# Control.net
KiCad netlist of a schematic drawn in Altium Designer
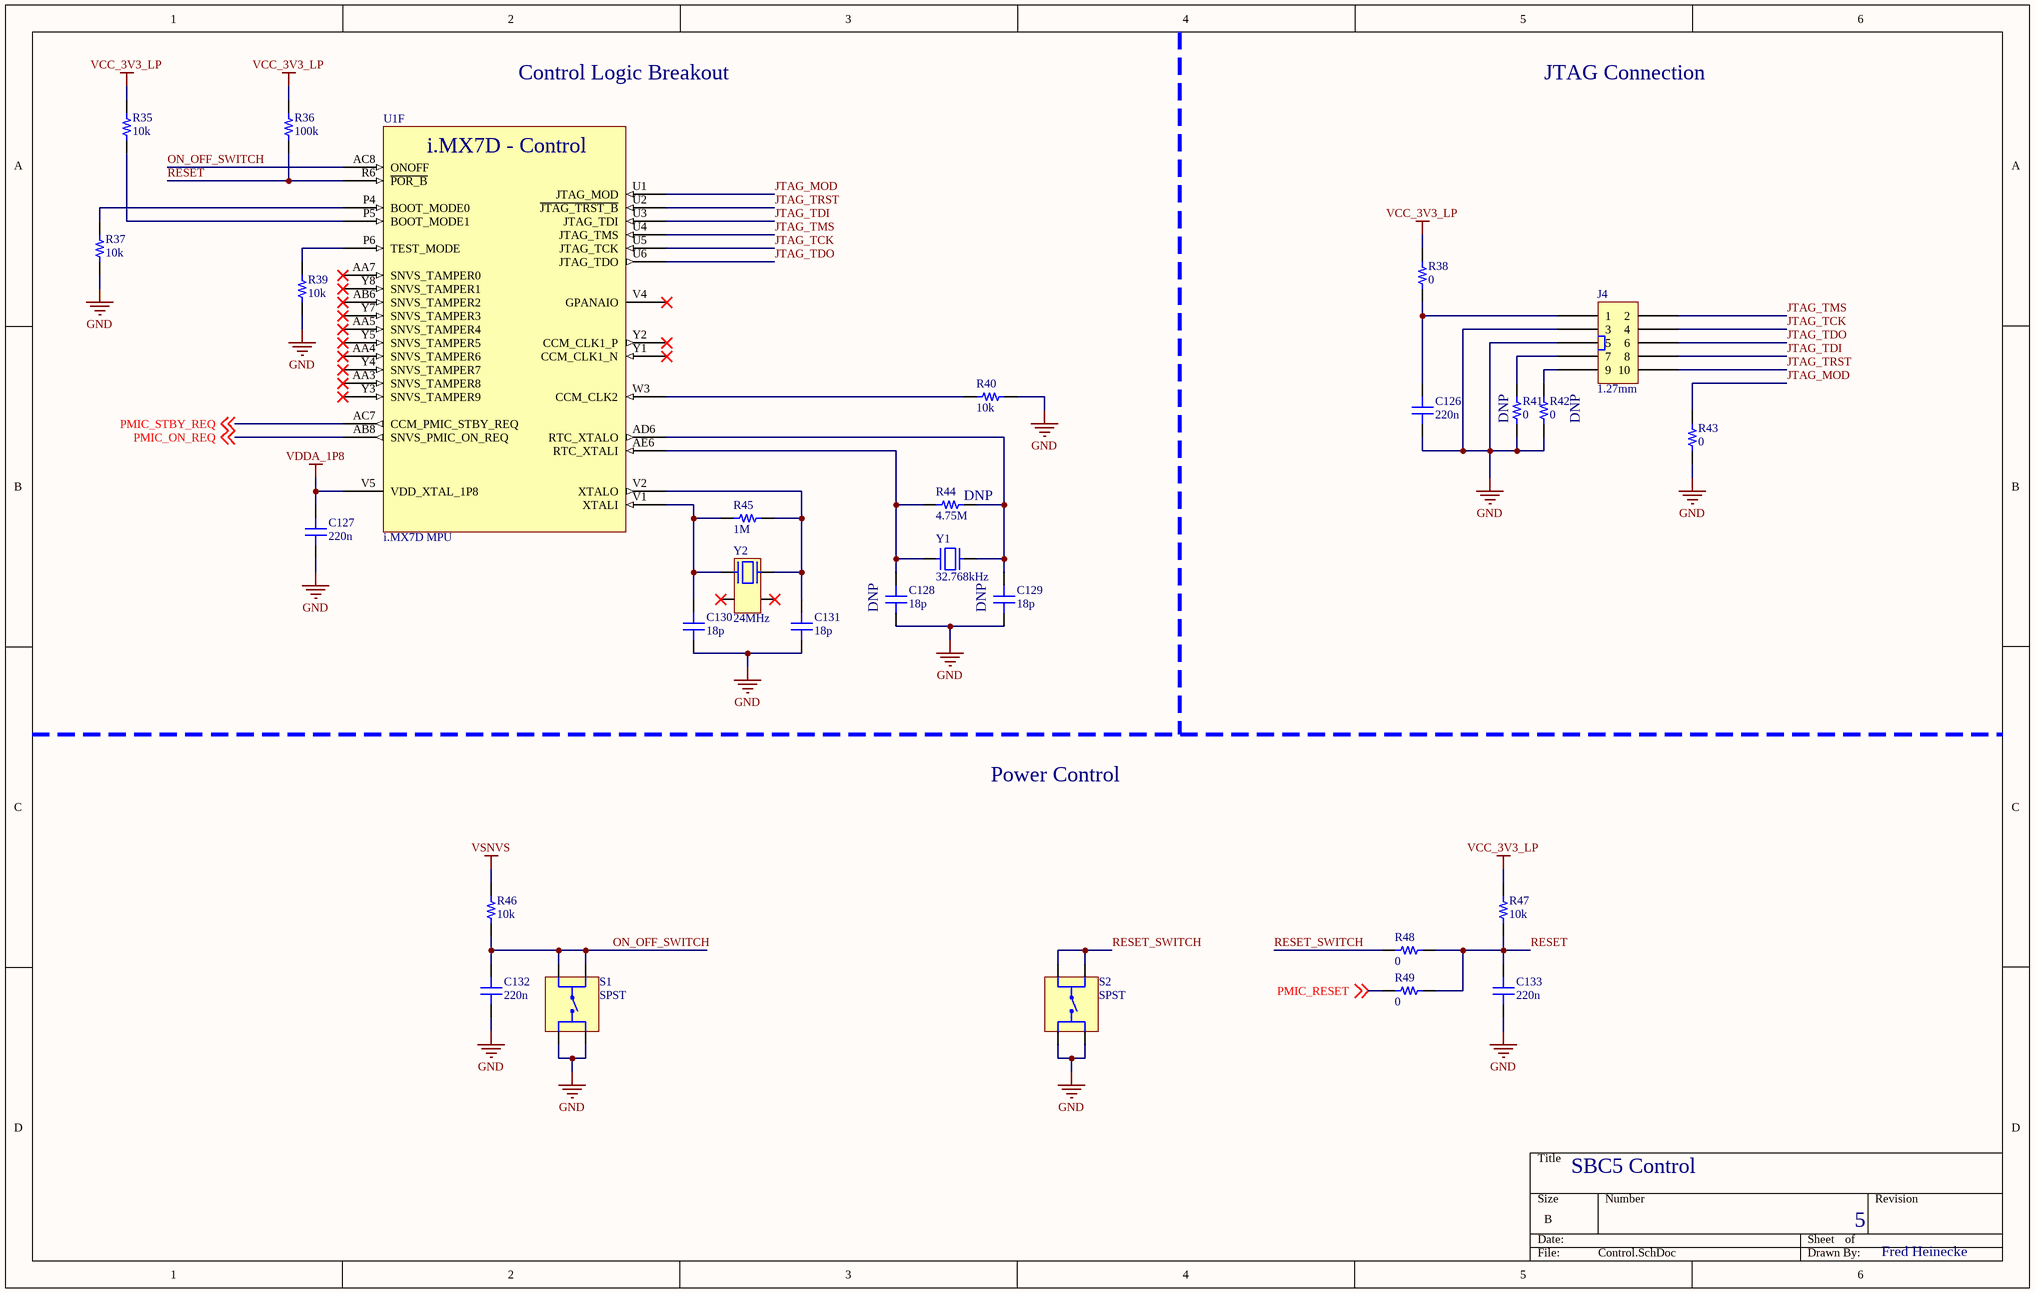
[diagram p0: Control.SchDoc]

(export (version "E")
  (design (tool "Eeschema 10.0.6"))
  (components
    (comp (ref "C126")
      (value "220n")
      (footprint "C0201")
      (description "Cap Ceramic Monolithic 0.22uF 16VDC 10% SMD Paper T/R")
      (fields
        (field (name "MANUFACTURER") "Murata")
        (field (name "MANUFACTURER PART NUMBER") "GRM033R61C224KE14D")
      )
      (libsource (lib "SBC5") (part "GRM033R61C224KE14D"))
    )
    (comp (ref "C127")
      (value "220n")
      (footprint "C0201")
      (description "Cap Ceramic Monolithic 0.22uF 16VDC 10% SMD Paper T/R")
      (fields
        (field (name "MANUFACTURER") "Murata")
        (field (name "MANUFACTURER PART NUMBER") "GRM033R61C224KE14D")
      )
      (libsource (lib "SBC5") (part "GRM033R61C224KE14D"))
    )
    (comp (ref "C128")
      (value "18p")
      (footprint "C0402")
      (description "CAP CER 18PF 50V C0G/NP0 0402")
      (fields
        (field (name "MANUFACTURER") "Samsung")
        (field (name "MANUFACTURER PART NUMBER") "CL05C180JB5NNNC")
      )
      (libsource (lib "SBC5") (part "CL05C180JB5NNNC"))
    )
    (comp (ref "C129")
      (value "18p")
      (footprint "C0402")
      (description "CAP CER 18PF 50V C0G/NP0 0402")
      (fields
        (field (name "MANUFACTURER") "Samsung")
        (field (name "MANUFACTURER PART NUMBER") "CL05C180JB5NNNC")
      )
      (libsource (lib "SBC5") (part "CL05C180JB5NNNC"))
    )
    (comp (ref "C130")
      (value "18p")
      (footprint "C0402")
      (description "CAP CER 18PF 50V C0G/NP0 0402")
      (fields
        (field (name "MANUFACTURER") "Samsung")
        (field (name "MANUFACTURER PART NUMBER") "CL05C180JB5NNNC")
      )
      (libsource (lib "SBC5") (part "CL05C180JB5NNNC"))
    )
    (comp (ref "C131")
      (value "18p")
      (footprint "C0402")
      (description "CAP CER 18PF 50V C0G/NP0 0402")
      (fields
        (field (name "MANUFACTURER") "Samsung")
        (field (name "MANUFACTURER PART NUMBER") "CL05C180JB5NNNC")
      )
      (libsource (lib "SBC5") (part "CL05C180JB5NNNC"))
    )
    (comp (ref "C132")
      (value "220n")
      (footprint "C0201")
      (description "Cap Ceramic Monolithic 0.22uF 16VDC 10% SMD Paper T/R")
      (fields
        (field (name "MANUFACTURER") "Murata")
        (field (name "MANUFACTURER PART NUMBER") "GRM033R61C224KE14D")
      )
      (libsource (lib "SBC5") (part "GRM033R61C224KE14D"))
    )
    (comp (ref "C133")
      (value "220n")
      (footprint "C0201")
      (description "Cap Ceramic Monolithic 0.22uF 16VDC 10% SMD Paper T/R")
      (fields
        (field (name "MANUFACTURER") "Murata")
        (field (name "MANUFACTURER PART NUMBER") "GRM033R61C224KE14D")
      )
      (libsource (lib "SBC5") (part "GRM033R61C224KE14D"))
    )
    (comp (ref "J4")
      (value "1.27mm")
      (footprint "20021521-00010T1LF")
      (description "CONN HEADER SMD 10POS 1.27MM")
      (fields
        (field (name "MANUFACTURER") "Amphenol FCI")
        (field (name "MANUFACTURER PART NUMBER") "20021521-00010T1LF")
      )
      (libsource (lib "SBC5") (part "20021521-00010T1LF"))
    )
    (comp (ref "R35")
      (value "10k")
      (footprint "R0201")
      (description "RES 10K OHM 1% 1/20W 0201")
      (fields
        (field (name "MANUFACTURER") "Stackpole Electronics")
        (field (name "MANUFACTURER PART NUMBER") "RMCF0201FT10K0")
      )
      (libsource (lib "SBC5") (part "RMCF0201FT10K0"))
    )
    (comp (ref "R36")
      (value "100k")
      (footprint "R0201")
      (description "PANASONIC - ERJ1GNF1003C - RES, 100K, 1%, 0.05W, 0201, THICK FILM")
      (fields
        (field (name "MANUFACTURER") "Panasonic")
        (field (name "MANUFACTURER PART NUMBER") "ERJ-1GNF1003C")
      )
      (libsource (lib "SBC5") (part "ERJ-1GNF1003C"))
    )
    (comp (ref "R37")
      (value "10k")
      (footprint "R0201")
      (description "RES 10K OHM 1% 1/20W 0201")
      (fields
        (field (name "MANUFACTURER") "Stackpole Electronics")
        (field (name "MANUFACTURER PART NUMBER") "RMCF0201FT10K0")
      )
      (libsource (lib "SBC5") (part "RMCF0201FT10K0"))
    )
    (comp (ref "R38")
      (value "0")
      (footprint "R1210")
      (description "RES 0.0 OHM 1/2W 1210 SMD")
      (fields
        (field (name "MANUFACTURER") "Stackpole Electronics")
        (field (name "MANUFACTURER PART NUMBER") "RMCF1210ZT0R00")
      )
      (libsource (lib "SBC5") (part "RMCF1210ZT0R00"))
    )
    (comp (ref "R39")
      (value "10k")
      (footprint "R0201")
      (description "RES 10K OHM 1% 1/20W 0201")
      (fields
        (field (name "MANUFACTURER") "Stackpole Electronics")
        (field (name "MANUFACTURER PART NUMBER") "RMCF0201FT10K0")
      )
      (libsource (lib "SBC5") (part "RMCF0201FT10K0"))
    )
    (comp (ref "R40")
      (value "10k")
      (footprint "R0201")
      (description "RES 10K OHM 1% 1/20W 0201")
      (fields
        (field (name "MANUFACTURER") "Stackpole Electronics")
        (field (name "MANUFACTURER PART NUMBER") "RMCF0201FT10K0")
      )
      (libsource (lib "SBC5") (part "RMCF0201FT10K0"))
    )
    (comp (ref "R41")
      (value "0")
      (footprint "R0402")
      (description "RES 0 OHM JUMPER 1/16W 0402")
      (fields
        (field (name "MANUFACTURER") "Stackpole Electronics")
        (field (name "MANUFACTURER PART NUMBER") "RMCF0402ZT0R00")
      )
      (libsource (lib "SBC5") (part "RMCF0402ZT0R00"))
    )
    (comp (ref "R42")
      (value "0")
      (footprint "R0402")
      (description "RES 0 OHM JUMPER 1/16W 0402")
      (fields
        (field (name "MANUFACTURER") "Stackpole Electronics")
        (field (name "MANUFACTURER PART NUMBER") "RMCF0402ZT0R00")
      )
      (libsource (lib "SBC5") (part "RMCF0402ZT0R00"))
    )
    (comp (ref "R43")
      (value "0")
      (footprint "R0402")
      (description "RES 0 OHM JUMPER 1/16W 0402")
      (fields
        (field (name "MANUFACTURER") "Stackpole Electronics")
        (field (name "MANUFACTURER PART NUMBER") "RMCF0402ZT0R00")
      )
      (libsource (lib "SBC5") (part "RMCF0402ZT0R00"))
    )
    (comp (ref "R44")
      (value "4.75M")
      (footprint "R0402")
      (description "Thick Film Resistors - SMD 4.75M OHM 1%")
      (fields
        (field (name "MANUFACTURER") "Yageo")
        (field (name "MANUFACTURER PART NUMBER") "RC0402FR-074M75L")
      )
      (libsource (lib "SBC5") (part "RC0402FR-074M75L"))
    )
    (comp (ref "R45")
      (value "1M")
      (footprint "R0402")
      (description "RES SMD 1M OHM 1% 1/16W 0402")
      (fields
        (field (name "MANUFACTURER") "Yageo")
        (field (name "MANUFACTURER PART NUMBER") "RC0402FR-071ML")
      )
      (libsource (lib "SBC5") (part "RC0402FR-071ML"))
    )
    (comp (ref "R46")
      (value "10k")
      (footprint "R0201")
      (description "RES 10K OHM 1% 1/20W 0201")
      (fields
        (field (name "MANUFACTURER") "Stackpole Electronics")
        (field (name "MANUFACTURER PART NUMBER") "RMCF0201FT10K0")
      )
      (libsource (lib "SBC5") (part "RMCF0201FT10K0"))
    )
    (comp (ref "R47")
      (value "10k")
      (footprint "R0201")
      (description "RES 10K OHM 1% 1/20W 0201")
      (fields
        (field (name "MANUFACTURER") "Stackpole Electronics")
        (field (name "MANUFACTURER PART NUMBER") "RMCF0201FT10K0")
      )
      (libsource (lib "SBC5") (part "RMCF0201FT10K0"))
    )
    (comp (ref "R48")
      (value "0")
      (footprint "R0402")
      (description "RES 0 OHM JUMPER 1/16W 0402")
      (fields
        (field (name "MANUFACTURER") "Stackpole Electronics")
        (field (name "MANUFACTURER PART NUMBER") "RMCF0402ZT0R00")
      )
      (libsource (lib "SBC5") (part "RMCF0402ZT0R00"))
    )
    (comp (ref "R49")
      (value "0")
      (footprint "R0402")
      (description "RES 0 OHM JUMPER 1/16W 0402")
      (fields
        (field (name "MANUFACTURER") "Stackpole Electronics")
        (field (name "MANUFACTURER PART NUMBER") "RMCF0402ZT0R00")
      )
      (libsource (lib "SBC5") (part "RMCF0402ZT0R00"))
    )
    (comp (ref "S1")
      (value "SPST")
      (footprint "1825910-7")
      (fields
        (field (name "MANUFACTURER") "TE Connectivity")
        (field (name "MANUFACTURER PART NUMBER") "1825910-7")
      )
      (libsource (lib "SBC5") (part "1825910-7"))
    )
    (comp (ref "S2")
      (value "SPST")
      (footprint "1825910-7")
      (fields
        (field (name "MANUFACTURER") "TE Connectivity")
        (field (name "MANUFACTURER PART NUMBER") "1825910-7")
      )
      (libsource (lib "SBC5") (part "1825910-7"))
    )
    (comp (ref "U1")
      (value "i.MX7D MPU")
      (footprint "BGA541C75P25X25_1900X1900X140")
      (description "Heterogeneous Multicore Processing Architecture")
      (fields
        (field (name "MANUFACTURER") "NXP Freescale")
        (field (name "MANUFACTURER PART NUMBER") "MCIMX7D2DVM12SD")
      )
      (libsource (lib "SBC5") (part "MCIMX7D2DVM12SD"))
    )
    (comp (ref "Y1")
      (value "32.768kHz")
      (footprint "CM7V-T1A")
      (description "32.768 kHz crystal oscillator, 12.5 pF 50k ESR")
      (fields
        (field (name "MANUFACTURER") "Micro Crystal")
        (field (name "MANUFACTURER PART NUMBER") "CM7VT1A-LOWESR-32.768KHZ-12.5PF-20-TA-QC")
      )
      (libsource (lib "SBC5") (part "CM7VT1A-LOWESR-32.768KHZ-12.5PF-20-TA-QC"))
    )
    (comp (ref "Y2")
      (value "24MHz")
      (footprint "FQ5032B")
      (description "Crystal 24MHz ±30ppm (Tol) ±30ppm (Stability) 20pF FUND 50Ohm 4-Pin SMD T/R")
      (fields
        (field (name "MANUFACTURER") "Fox Electronics")
        (field (name "MANUFACTURER PART NUMBER") "FC5BQCCMC24.0-T1")
      )
      (libsource (lib "SBC5") (part "FC5BQCCMC24.0-T1"))
    )
  )
  (nets
    (net (code "1") (name "/JTAG_MOD") (class "Default")
      (node (ref "R43") (pin "2") (pinfunction "2_2") (pintype "passive"))
      (node (ref "U1") (pin "U1") (pinfunction "JTAG_MOD_U1") (pintype "input"))
    )
    (net (code "2") (name "/JTAG_TCK") (class "Default")
      (node (ref "J4") (pin "4") (pinfunction "4_4") (pintype "passive"))
      (node (ref "U1") (pin "U5") (pinfunction "JTAG_TCK_U5") (pintype "input"))
    )
    (net (code "3") (name "/JTAG_TDI") (class "Default")
      (node (ref "J4") (pin "8") (pinfunction "8_8") (pintype "passive"))
      (node (ref "U1") (pin "U3") (pinfunction "JTAG_TDI_U3") (pintype "input"))
    )
    (net (code "4") (name "/JTAG_TDO") (class "Default")
      (node (ref "J4") (pin "6") (pinfunction "6_6") (pintype "passive"))
      (node (ref "U1") (pin "U6") (pinfunction "JTAG_TDO_U6") (pintype "output"))
    )
    (net (code "5") (name "/JTAG_TMS") (class "Default")
      (node (ref "J4") (pin "2") (pinfunction "2_2") (pintype "passive"))
      (node (ref "U1") (pin "U4") (pinfunction "JTAG_TMS_U4") (pintype "input"))
    )
    (net (code "6") (name "/JTAG_TRST") (class "Default")
      (node (ref "J4") (pin "10") (pinfunction "10_10") (pintype "passive"))
      (node (ref "U1") (pin "U2") (pinfunction "~{JTAG_TRST_B}_U2") (pintype "input"))
    )
    (net (code "7") (name "/ON_OFF_SWITCH") (class "Default")
      (node (ref "C132") (pin "2") (pinfunction "2_2") (pintype "passive"))
      (node (ref "R46") (pin "1") (pinfunction "1_1") (pintype "passive"))
      (node (ref "S1") (pin "1") (pintype "passive"))
      (node (ref "S1") (pin "2") (pintype "passive"))
      (node (ref "U1") (pin "AC8") (pinfunction "ONOFF_AC8") (pintype "input"))
    )
    (net (code "8") (name "/RESET") (class "Default")
      (node (ref "C133") (pin "2") (pinfunction "2_2") (pintype "passive"))
      (node (ref "R36") (pin "1") (pinfunction "1_1") (pintype "passive"))
      (node (ref "R47") (pin "1") (pinfunction "1_1") (pintype "passive"))
      (node (ref "R48") (pin "2") (pinfunction "2_2") (pintype "passive"))
      (node (ref "R49") (pin "2") (pinfunction "2_2") (pintype "passive"))
      (node (ref "U1") (pin "R6") (pinfunction "~{POR_B}_R6") (pintype "input"))
    )
    (net (code "9") (name "/RESET_SWITCH") (class "Default")
      (node (ref "R48") (pin "1") (pinfunction "1_1") (pintype "passive"))
      (node (ref "S2") (pin "1") (pintype "passive"))
      (node (ref "S2") (pin "2") (pintype "passive"))
    )
    (net (code "10") (name "GND") (class "Default")
      (node (ref "C126") (pin "1") (pinfunction "1_1") (pintype "passive"))
      (node (ref "C127") (pin "1") (pinfunction "1_1") (pintype "passive"))
      (node (ref "C128") (pin "1") (pinfunction "1_1") (pintype "passive"))
      (node (ref "C129") (pin "1") (pinfunction "1_1") (pintype "passive"))
      (node (ref "C130") (pin "1") (pinfunction "1_1") (pintype "passive"))
      (node (ref "C131") (pin "1") (pinfunction "1_1") (pintype "passive"))
      (node (ref "C132") (pin "1") (pinfunction "1_1") (pintype "passive"))
      (node (ref "C133") (pin "1") (pinfunction "1_1") (pintype "passive"))
      (node (ref "J4") (pin "3") (pinfunction "3_3") (pintype "passive"))
      (node (ref "J4") (pin "5") (pinfunction "5_5") (pintype "passive"))
      (node (ref "R37") (pin "1") (pinfunction "1_1") (pintype "passive"))
      (node (ref "R39") (pin "1") (pinfunction "1_1") (pintype "passive"))
      (node (ref "R40") (pin "2") (pinfunction "2_2") (pintype "passive"))
      (node (ref "R41") (pin "1") (pinfunction "1_1") (pintype "passive"))
      (node (ref "R42") (pin "1") (pinfunction "1_1") (pintype "passive"))
      (node (ref "R43") (pin "1") (pinfunction "1_1") (pintype "passive"))
      (node (ref "S1") (pin "3") (pintype "passive"))
      (node (ref "S1") (pin "4") (pintype "passive"))
      (node (ref "S2") (pin "3") (pintype "passive"))
      (node (ref "S2") (pin "4") (pintype "passive"))
    )
    (net (code "11") (name "Net-(C126-Pad2)") (class "Default")
      (node (ref "C126") (pin "2") (pinfunction "2_2") (pintype "passive"))
      (node (ref "J4") (pin "1") (pinfunction "1_1") (pintype "passive"))
      (node (ref "R38") (pin "1") (pinfunction "1_1") (pintype "passive"))
    )
    (net (code "12") (name "Net-(J4-Pad7)") (class "Default")
      (node (ref "J4") (pin "7") (pinfunction "7_7") (pintype "passive"))
      (node (ref "R41") (pin "2") (pinfunction "2_2") (pintype "passive"))
    )
    (net (code "13") (name "Net-(J4-Pad9)") (class "Default")
      (node (ref "J4") (pin "9") (pinfunction "9_9") (pintype "passive"))
      (node (ref "R42") (pin "2") (pinfunction "2_2") (pintype "passive"))
    )
    (net (code "14") (name "Net-(U1F-BOOT_MODE0)") (class "Default")
      (node (ref "R37") (pin "2") (pinfunction "2_2") (pintype "passive"))
      (node (ref "U1") (pin "P4") (pinfunction "BOOT_MODE0_P4") (pintype "input"))
    )
    (net (code "15") (name "Net-(U1F-BOOT_MODE1)") (class "Default")
      (node (ref "R35") (pin "1") (pinfunction "1_1") (pintype "passive"))
      (node (ref "U1") (pin "P5") (pinfunction "BOOT_MODE1_P5") (pintype "input"))
    )
    (net (code "16") (name "Net-(U1F-CCM_CLK2)") (class "Default")
      (node (ref "R40") (pin "1") (pinfunction "1_1") (pintype "passive"))
      (node (ref "U1") (pin "W3") (pinfunction "CCM_CLK2_W3") (pintype "input"))
    )
    (net (code "17") (name "Net-(U1F-RTC_XTALI)") (class "Default")
      (node (ref "C128") (pin "2") (pinfunction "2_2") (pintype "passive"))
      (node (ref "R44") (pin "1") (pinfunction "1_1") (pintype "passive"))
      (node (ref "U1") (pin "AE6") (pinfunction "RTC_XTALI_AE6") (pintype "input"))
      (node (ref "Y1") (pin "1") (pinfunction "1_1") (pintype "passive"))
    )
    (net (code "18") (name "Net-(U1F-RTC_XTALO)") (class "Default")
      (node (ref "C129") (pin "2") (pinfunction "2_2") (pintype "passive"))
      (node (ref "R44") (pin "2") (pinfunction "2_2") (pintype "passive"))
      (node (ref "U1") (pin "AD6") (pinfunction "RTC_XTALO_AD6") (pintype "output"))
      (node (ref "Y1") (pin "2") (pinfunction "2_2") (pintype "passive"))
    )
    (net (code "19") (name "Net-(U1F-TEST_MODE)") (class "Default")
      (node (ref "R39") (pin "2") (pinfunction "2_2") (pintype "passive"))
      (node (ref "U1") (pin "P6") (pinfunction "TEST_MODE_P6") (pintype "input"))
    )
    (net (code "20") (name "Net-(U1F-XTALI)") (class "Default")
      (node (ref "C130") (pin "2") (pinfunction "2_2") (pintype "passive"))
      (node (ref "R45") (pin "1") (pinfunction "1_1") (pintype "passive"))
      (node (ref "U1") (pin "V1") (pinfunction "XTALI_V1") (pintype "input"))
      (node (ref "Y2") (pin "1") (pinfunction "1_1") (pintype "passive"))
    )
    (net (code "21") (name "Net-(U1F-XTALO)") (class "Default")
      (node (ref "C131") (pin "2") (pinfunction "2_2") (pintype "passive"))
      (node (ref "R45") (pin "2") (pinfunction "2_2") (pintype "passive"))
      (node (ref "U1") (pin "V2") (pinfunction "XTALO_V2") (pintype "output"))
      (node (ref "Y2") (pin "3") (pinfunction "3_3") (pintype "passive"))
    )
    (net (code "22") (name "PMIC_ON_REQ") (class "Default")
      (node (ref "U1") (pin "AB8") (pinfunction "SNVS_PMIC_ON_REQ_AB8") (pintype "output"))
    )
    (net (code "23") (name "PMIC_RESET") (class "Default")
      (node (ref "R49") (pin "1") (pinfunction "1_1") (pintype "passive"))
    )
    (net (code "24") (name "PMIC_STBY_REQ") (class "Default")
      (node (ref "U1") (pin "AC7") (pinfunction "CCM_PMIC_STBY_REQ_AC7") (pintype "output"))
    )
    (net (code "25") (name "VCC_3V3_LP") (class "Default")
      (node (ref "R35") (pin "2") (pinfunction "2_2") (pintype "passive"))
      (node (ref "R36") (pin "2") (pinfunction "2_2") (pintype "passive"))
      (node (ref "R38") (pin "2") (pinfunction "2_2") (pintype "passive"))
      (node (ref "R47") (pin "2") (pinfunction "2_2") (pintype "passive"))
    )
    (net (code "26") (name "VDDA_1P8") (class "Default")
      (node (ref "C127") (pin "2") (pinfunction "2_2") (pintype "passive"))
      (node (ref "U1") (pin "V5") (pinfunction "VDD_XTAL_1P8_V5") (pintype "passive"))
    )
    (net (code "27") (name "VSNVS") (class "Default")
      (node (ref "R46") (pin "2") (pinfunction "2_2") (pintype "passive"))
    )
    (net (code "28") (name "unconnected-(U1F-CCM_CLK1_N-PadY1)") (class "Default")
      (node (ref "U1") (pin "Y1") (pinfunction "CCM_CLK1_N_Y1") (pintype "input+no_connect"))
    )
    (net (code "29") (name "unconnected-(U1F-CCM_CLK1_P-PadY2)") (class "Default")
      (node (ref "U1") (pin "Y2") (pinfunction "CCM_CLK1_P_Y2") (pintype "output+no_connect"))
    )
    (net (code "30") (name "unconnected-(U1F-GPANAIO-PadV4)") (class "Default")
      (node (ref "U1") (pin "V4") (pinfunction "GPANAIO_V4") (pintype "passive+no_connect"))
    )
    (net (code "31") (name "unconnected-(U1F-SNVS_TAMPER0-PadAA7)") (class "Default")
      (node (ref "U1") (pin "AA7") (pinfunction "SNVS_TAMPER0_AA7") (pintype "input+no_connect"))
    )
    (net (code "32") (name "unconnected-(U1F-SNVS_TAMPER1-PadY8)") (class "Default")
      (node (ref "U1") (pin "Y8") (pinfunction "SNVS_TAMPER1_Y8") (pintype "input+no_connect"))
    )
    (net (code "33") (name "unconnected-(U1F-SNVS_TAMPER2-PadAB6)") (class "Default")
      (node (ref "U1") (pin "AB6") (pinfunction "SNVS_TAMPER2_AB6") (pintype "input+no_connect"))
    )
    (net (code "34") (name "unconnected-(U1F-SNVS_TAMPER3-PadY7)") (class "Default")
      (node (ref "U1") (pin "Y7") (pinfunction "SNVS_TAMPER3_Y7") (pintype "input+no_connect"))
    )
    (net (code "35") (name "unconnected-(U1F-SNVS_TAMPER4-PadAA5)") (class "Default")
      (node (ref "U1") (pin "AA5") (pinfunction "SNVS_TAMPER4_AA5") (pintype "input+no_connect"))
    )
    (net (code "36") (name "unconnected-(U1F-SNVS_TAMPER5-PadY5)") (class "Default")
      (node (ref "U1") (pin "Y5") (pinfunction "SNVS_TAMPER5_Y5") (pintype "input+no_connect"))
    )
    (net (code "37") (name "unconnected-(U1F-SNVS_TAMPER6-PadAA4)") (class "Default")
      (node (ref "U1") (pin "AA4") (pinfunction "SNVS_TAMPER6_AA4") (pintype "input+no_connect"))
    )
    (net (code "38") (name "unconnected-(U1F-SNVS_TAMPER7-PadY4)") (class "Default")
      (node (ref "U1") (pin "Y4") (pinfunction "SNVS_TAMPER7_Y4") (pintype "input+no_connect"))
    )
    (net (code "39") (name "unconnected-(U1F-SNVS_TAMPER8-PadAA3)") (class "Default")
      (node (ref "U1") (pin "AA3") (pinfunction "SNVS_TAMPER8_AA3") (pintype "input+no_connect"))
    )
    (net (code "40") (name "unconnected-(U1F-SNVS_TAMPER9-PadY3)") (class "Default")
      (node (ref "U1") (pin "Y3") (pinfunction "SNVS_TAMPER9_Y3") (pintype "input+no_connect"))
    )
    (net (code "41") (name "unconnected-(Y2-Pad2)") (class "Default")
      (node (ref "Y2") (pin "2") (pinfunction "2_2") (pintype "passive+no_connect"))
    )
    (net (code "42") (name "unconnected-(Y2-Pad4)") (class "Default")
      (node (ref "Y2") (pin "4") (pinfunction "4_4") (pintype "passive+no_connect"))
    )
  )
)
